# RF_Antenna_Switch.net
KiCad netlist of a schematic drawn in Altium Designer
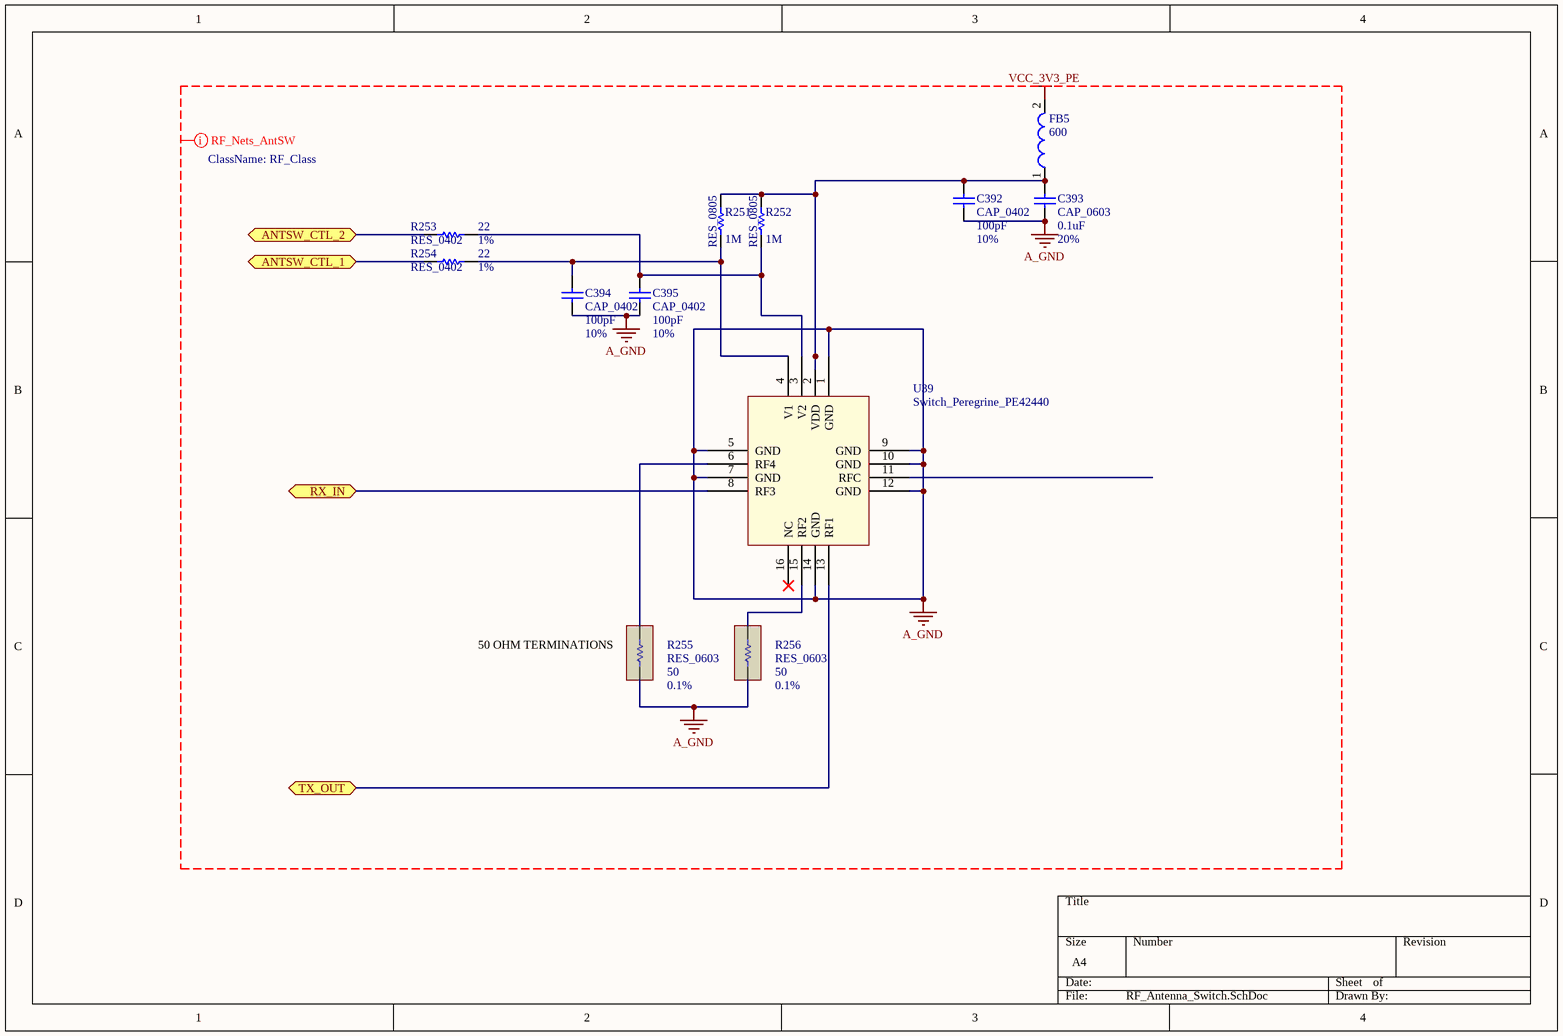
[diagram p0: RF_Antenna_Switch.SchDoc]

(export (version "E")
  (design (tool "Eeschema 10.0.6"))
  (components
    (comp (ref "C392")
      (value "CAP_0402")
      (footprint "CAPC0402(1005)60_N")
      (description "100pF, ceramic, 10% 6.3V X7R, 0402")
      (fields
        (field (name "ALTIUM_VALUE") "100pF")
        (field (name "TOLERANCE") "10%")
        (field (name "PART NUMBER") "04026C101KAT2A")
        (field (name "MANUFACTURER") "AVX Corporation")
      )
      (libsource (lib "COMRAD_Database") (part "CAP_0402"))
    )
    (comp (ref "C393")
      (value "CAP_0603")
      (footprint "CAPC0603(1608)100_N")
      (description "CAP CER 0.1UF 6.3V 20% X7R 0603")
      (fields
        (field (name "ALTIUM_VALUE") "0.1uF")
        (field (name "TOLERANCE") "20%")
        (field (name "PART NUMBER") "6R3X14W104MV4T")
        (field (name "MANUFACTURER") "Johanson Dielectrics Inc")
      )
      (libsource (lib "COMRAD_Database") (part "CAP_0603"))
    )
    (comp (ref "C394")
      (value "CAP_0402")
      (footprint "CAPC0402(1005)60_N")
      (description "100pF, ceramic, 10% 6.3V X7R, 0402")
      (fields
        (field (name "ALTIUM_VALUE") "100pF")
        (field (name "TOLERANCE") "10%")
        (field (name "PART NUMBER") "04026C101KAT2A")
        (field (name "MANUFACTURER") "AVX Corporation")
      )
      (libsource (lib "COMRAD_Database") (part "CAP_0402"))
    )
    (comp (ref "C395")
      (value "CAP_0402")
      (footprint "CAPC0402(1005)60_N")
      (description "100pF, ceramic, 10% 6.3V X7R, 0402")
      (fields
        (field (name "ALTIUM_VALUE") "100pF")
        (field (name "TOLERANCE") "10%")
        (field (name "PART NUMBER") "04026C101KAT2A")
        (field (name "MANUFACTURER") "AVX Corporation")
      )
      (libsource (lib "COMRAD_Database") (part "CAP_0402"))
    )
    (comp (ref "FB5")
      (value "FerriteBead")
      (footprint "Inductor0402(1005)")
      (description "Ferrite 300mA 600ohm 0402")
      (fields
        (field (name "Z") "600")
        (field (name "PART NUMBER") "\"MMZ1005S601C\"")
        (field (name "MANUFACTURER") "TDK")
      )
      (libsource (lib "COMRAD_Database") (part "FerriteBead"))
    )
    (comp (ref "R251")
      (value "RES_0805")
      (footprint "RESC0805(2012)_N")
      (description "1M ohm, 5%, 1/8W, 0805")
      (fields
        (field (name "ALTIUM_VALUE") "1M")
        (field (name "TOLERANCE") "5%")
        (field (name "PART NUMBER") "9C08052A1004JLHFT")
      )
      (libsource (lib "COMRAD_Database") (part "RES_0805"))
    )
    (comp (ref "R252")
      (value "RES_0805")
      (footprint "RESC0805(2012)_N")
      (description "1M ohm, 5%, 1/8W, 0805")
      (fields
        (field (name "ALTIUM_VALUE") "1M")
        (field (name "TOLERANCE") "5%")
        (field (name "PART NUMBER") "9C08052A1004JLHFT")
      )
      (libsource (lib "COMRAD_Database") (part "RES_0805"))
    )
    (comp (ref "R253")
      (value "RES_0402")
      (footprint "RESC0402(1005)_N")
      (description "RES 22.0 OHM 1/10W 1% 0402 SMD")
      (fields
        (field (name "ALTIUM_VALUE") "22")
        (field (name "TOLERANCE") "1%")
        (field (name "PART NUMBER") "ERJ-2RKF22R0X")
        (field (name "MANUFACTURER") "Panasonic Electronic Components")
      )
      (libsource (lib "COMRAD_Database") (part "RES_0402"))
    )
    (comp (ref "R254")
      (value "RES_0402")
      (footprint "RESC0402(1005)_N")
      (description "RES 22.0 OHM 1/10W 1% 0402 SMD")
      (fields
        (field (name "ALTIUM_VALUE") "22")
        (field (name "TOLERANCE") "1%")
        (field (name "PART NUMBER") "ERJ-2RKF22R0X")
        (field (name "MANUFACTURER") "Panasonic Electronic Components")
      )
      (libsource (lib "COMRAD_Database") (part "RES_0402"))
    )
    (comp (ref "R255")
      (value "RES_0603")
      (footprint "RESC0603(1608)_N")
      (description "RES 50 OHM 125MW .1% 0603 SMD")
      (fields
        (field (name "ALTIUM_VALUE") "50")
        (field (name "TOLERANCE") "0.1%")
        (field (name "PART NUMBER") "FC0603E50R0BTBST1")
        (field (name "MANUFACTURER") "Vishay Thin Film")
      )
      (libsource (lib "COMRAD_Database") (part "RES_0603"))
    )
    (comp (ref "R256")
      (value "RES_0603")
      (footprint "RESC0603(1608)_N")
      (description "RES 50 OHM 125MW .1% 0603 SMD")
      (fields
        (field (name "ALTIUM_VALUE") "50")
        (field (name "TOLERANCE") "0.1%")
        (field (name "PART NUMBER") "FC0603E50R0BTBST1")
        (field (name "MANUFACTURER") "Vishay Thin Film")
      )
      (libsource (lib "COMRAD_Database") (part "RES_0603"))
    )
    (comp (ref "U39")
      (value "Switch_Peregrine_PE42440")
      (footprint "Switch_Peregrine_PE42440_16-QFN")
      (description "SP4T UltraCMOS RF Switch, 50 - 3000 MHz, Isolation 34dB, Insertion loss 0.45 dB,16QFN")
      (fields (field (name "PART NUMBER") "PE42440MLBB-Z") (field (name "MANUFACTURER") "Peregrine"))
      (libsource (lib "COMRAD_Database") (part "Switch_Peregrine_PE42440"))
    )
  )
  (nets
    (net (code "1") (name "/ANTSW_CTL_1") (class "Default")
      (node (ref "R254") (pin "1") (pinfunction "1_1") (pintype "passive"))
    )
    (net (code "2") (name "/ANTSW_CTL_2") (class "Default")
      (node (ref "R253") (pin "1") (pinfunction "1_1") (pintype "passive"))
    )
    (net (code "3") (name "/RX_IN") (class "Default")
      (node (ref "U39") (pin "8") (pinfunction "RF3_8") (pintype "passive"))
    )
    (net (code "4") (name "/TX_OUT") (class "Default")
      (node (ref "U39") (pin "13") (pinfunction "RF1_13") (pintype "passive"))
    )
    (net (code "5") (name "A_GND") (class "Default")
      (node (ref "C392") (pin "1") (pinfunction "1_1") (pintype "passive"))
      (node (ref "C393") (pin "1") (pinfunction "1_1") (pintype "passive"))
      (node (ref "C394") (pin "1") (pinfunction "1_1") (pintype "passive"))
      (node (ref "C395") (pin "1") (pinfunction "1_1") (pintype "passive"))
      (node (ref "R255") (pin "1") (pinfunction "1_1") (pintype "passive"))
      (node (ref "R256") (pin "1") (pinfunction "1_1") (pintype "passive"))
      (node (ref "U39") (pin "1") (pinfunction "GND_1") (pintype "power_in"))
      (node (ref "U39") (pin "10") (pinfunction "GND_10") (pintype "power_in"))
      (node (ref "U39") (pin "12") (pinfunction "GND_12") (pintype "power_in"))
      (node (ref "U39") (pin "14") (pinfunction "GND_14") (pintype "power_in"))
      (node (ref "U39") (pin "5") (pinfunction "GND_5") (pintype "power_in"))
      (node (ref "U39") (pin "7") (pinfunction "GND_7") (pintype "power_in"))
      (node (ref "U39") (pin "9") (pinfunction "GND_9") (pintype "power_in"))
    )
    (net (code "6") (name "Net-(U39-RF2)") (class "Default")
      (node (ref "R256") (pin "2") (pinfunction "2_2") (pintype "passive"))
      (node (ref "U39") (pin "15") (pinfunction "RF2_15") (pintype "passive"))
    )
    (net (code "7") (name "Net-(U39-RF4)") (class "Default")
      (node (ref "R255") (pin "2") (pinfunction "2_2") (pintype "passive"))
      (node (ref "U39") (pin "6") (pinfunction "RF4_6") (pintype "passive"))
    )
    (net (code "8") (name "Net-(U39-V1)") (class "Default")
      (node (ref "C394") (pin "2") (pinfunction "2_2") (pintype "passive"))
      (node (ref "R251") (pin "1") (pinfunction "1_1") (pintype "passive"))
      (node (ref "R254") (pin "2") (pinfunction "2_2") (pintype "passive"))
      (node (ref "U39") (pin "4") (pinfunction "V1_4") (pintype "passive"))
    )
    (net (code "9") (name "Net-(U39-V2)") (class "Default")
      (node (ref "C395") (pin "2") (pinfunction "2_2") (pintype "passive"))
      (node (ref "R252") (pin "1") (pinfunction "1_1") (pintype "passive"))
      (node (ref "R253") (pin "2") (pinfunction "2_2") (pintype "passive"))
      (node (ref "U39") (pin "3") (pinfunction "V2_3") (pintype "passive"))
    )
    (net (code "10") (name "Net-(U39-VDD)") (class "Default")
      (node (ref "C392") (pin "2") (pinfunction "2_2") (pintype "passive"))
      (node (ref "C393") (pin "2") (pinfunction "2_2") (pintype "passive"))
      (node (ref "FB5") (pin "1") (pinfunction "1_1") (pintype "passive"))
      (node (ref "R251") (pin "2") (pinfunction "2_2") (pintype "passive"))
      (node (ref "R252") (pin "2") (pinfunction "2_2") (pintype "passive"))
      (node (ref "U39") (pin "2") (pinfunction "VDD_2") (pintype "power_in"))
    )
    (net (code "11") (name "VCC_3V3_PE") (class "Default")
      (node (ref "FB5") (pin "2") (pinfunction "2_2") (pintype "passive"))
    )
    (net (code "12") (name "unconnected-(U39-NC-Pad16)") (class "Default")
      (node (ref "U39") (pin "16") (pinfunction "NC_16") (pintype "passive+no_connect"))
    )
    (net (code "13") (name "unconnected-(U39-RFC-Pad11)") (class "Default")
      (node (ref "U39") (pin "11") (pinfunction "RFC_11") (pintype "passive"))
    )
  )
)
